# Sheet_1_2025-03-21.net
KiCad netlist of a schematic drawn in Altium Designer
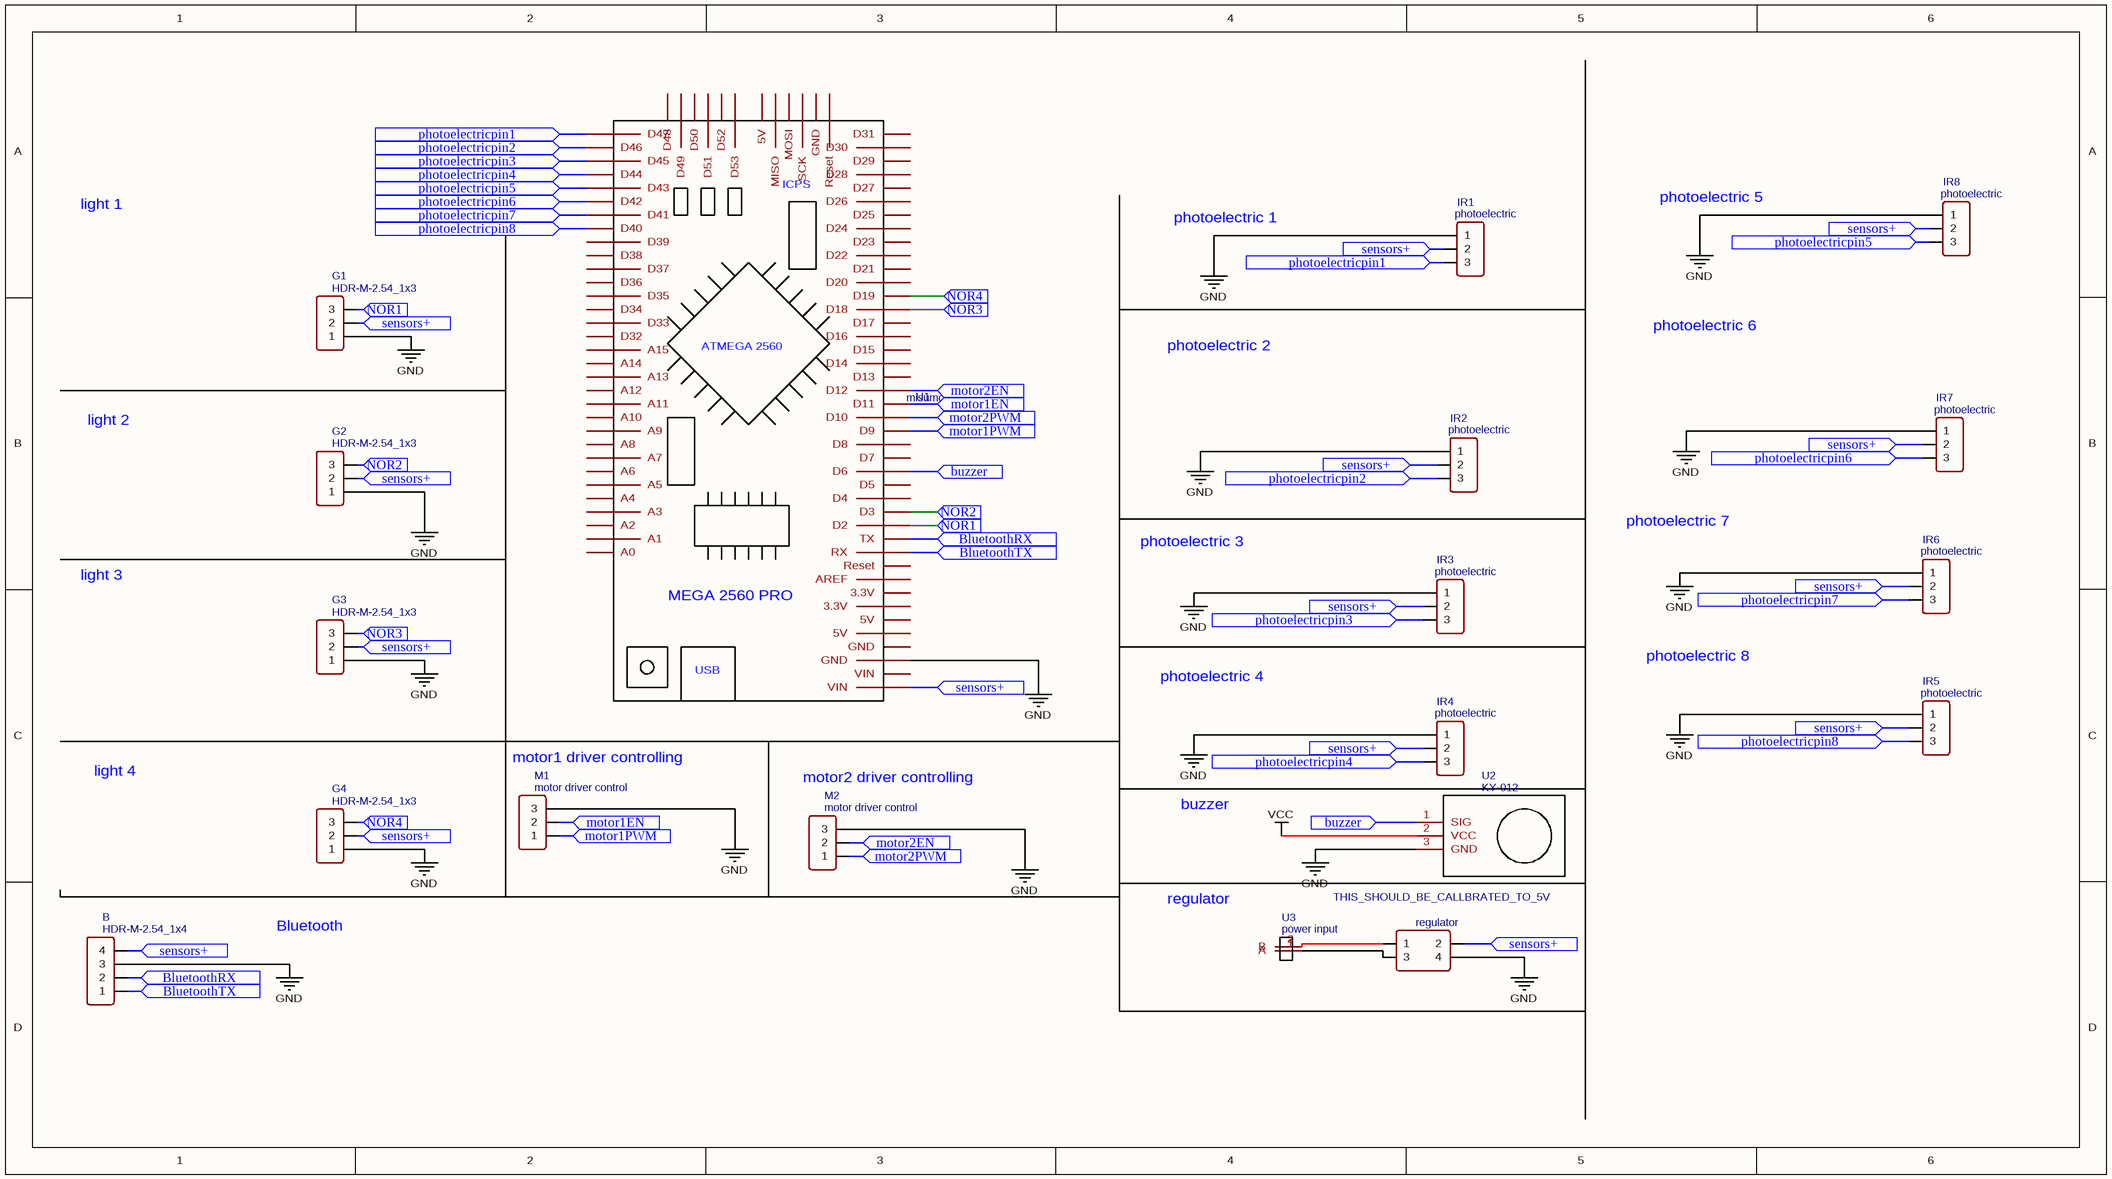
[diagram p0: Sheet_1_2025-03-21.schdoc]

(export (version "E")
  (design (tool "Eeschema 10.0.6"))
  (components
    (comp (ref "B")
      (value "HDR-M-2.54_1x4")
      (fields (field (name "CONTRIBUTOR") "LCEDA_Lib"))
      (libsource (lib "altium-import") (part "root_2_HDR-M-2.54_1x4_"))
    )
    (comp (ref "G1")
      (value "HDR-M-2.54_1x3")
      (fields (field (name "CONTRIBUTOR") "LCEDA_Lib"))
      (libsource (lib "altium-import") (part "root_2_HDR-M-2.54_1x3_"))
    )
    (comp (ref "G2")
      (value "HDR-M-2.54_1x3")
      (fields (field (name "CONTRIBUTOR") "LCEDA_Lib"))
      (libsource (lib "altium-import") (part "root_2_HDR-M-2.54_1x3_"))
    )
    (comp (ref "G3")
      (value "HDR-M-2.54_1x3")
      (fields (field (name "CONTRIBUTOR") "LCEDA_Lib"))
      (libsource (lib "altium-import") (part "root_2_HDR-M-2.54_1x3_"))
    )
    (comp (ref "G4")
      (value "HDR-M-2.54_1x3")
      (fields (field (name "CONTRIBUTOR") "LCEDA_Lib"))
      (libsource (lib "altium-import") (part "root_2_HDR-M-2.54_1x3_"))
    )
    (comp (ref "IR1")
      (value "photoelectric")
      (fields (field (name "CONTRIBUTOR") "LCEDA_Lib"))
      (libsource (lib "altium-import") (part "root_0_photoelectric_"))
    )
    (comp (ref "IR2")
      (value "photoelectric")
      (fields (field (name "CONTRIBUTOR") "LCEDA_Lib"))
      (libsource (lib "altium-import") (part "root_0_photoelectric_"))
    )
    (comp (ref "IR3")
      (value "photoelectric")
      (fields (field (name "CONTRIBUTOR") "LCEDA_Lib"))
      (libsource (lib "altium-import") (part "root_0_photoelectric_"))
    )
    (comp (ref "IR4")
      (value "photoelectric")
      (fields (field (name "CONTRIBUTOR") "LCEDA_Lib"))
      (libsource (lib "altium-import") (part "root_0_photoelectric_"))
    )
    (comp (ref "IR5")
      (value "photoelectric")
      (fields (field (name "CONTRIBUTOR") "LCEDA_Lib"))
      (libsource (lib "altium-import") (part "root_0_photoelectric_"))
    )
    (comp (ref "IR6")
      (value "photoelectric")
      (fields (field (name "CONTRIBUTOR") "LCEDA_Lib"))
      (libsource (lib "altium-import") (part "root_0_photoelectric_"))
    )
    (comp (ref "IR7")
      (value "photoelectric")
      (fields (field (name "CONTRIBUTOR") "LCEDA_Lib"))
      (libsource (lib "altium-import") (part "root_0_photoelectric_"))
    )
    (comp (ref "IR8")
      (value "photoelectric")
      (fields (field (name "CONTRIBUTOR") "LCEDA_Lib"))
      (libsource (lib "altium-import") (part "root_0_photoelectric_"))
    )
    (comp (ref "M1")
      (value "motor driver control")
      (fields (field (name "CONTRIBUTOR") "LCEDA_Lib"))
      (libsource (lib "altium-import") (part "root_2_motor driver control_"))
    )
    (comp (ref "M2")
      (value "motor driver control")
      (fields (field (name "CONTRIBUTOR") "LCEDA_Lib"))
      (libsource (lib "altium-import") (part "root_2_motor driver control_"))
    )
    (comp (ref "THIS_SHOULD_BE_CALLBRATED_TO_5V")
      (value "regulator")
      (fields (field (name "CONTRIBUTOR") "LCEDA_Lib"))
      (libsource (lib "altium-import") (part "root_0_regulator_"))
    )
    (comp (ref "U1")
      (value "misumo potente")
      (fields
        (field (name "MANUFACTURER PART") "Arduino Mega 2560 Pro Mini")
        (field (name "CONTRIBUTOR") "Mauricio Placito Lopez")
      )
      (libsource (lib "altium-import") (part "root_0_misumo potente_"))
    )
    (comp (ref "U2")
      (value "KY-012")
      (fields (field (name "CONTRIBUTOR") "Андрей Кошевой"))
      (libsource (lib "altium-import") (part "root_1_KY-012_"))
    )
    (comp (ref "U3")
      (value "power input")
      (fields
        (field (name "MANUFACTURER") "Phoenix Contact")
        (field (name "MANUFACTURER PART") "1725656")
        (field (name "CONTRIBUTOR") "sm.rial")
      )
      (libsource (lib "altium-import") (part "root_1_power input_"))
    )
  )
  (nets
    (net (code "1") (name "/BluetoothRX") (class "Default")
      (node (ref "B") (pin "2") (pinfunction "2_2") (pintype "passive"))
      (node (ref "U1") (pin "75") (pinfunction "TX_75") (pintype "passive"))
    )
    (net (code "2") (name "/BluetoothTX") (class "Default")
      (node (ref "B") (pin "1") (pinfunction "1_1") (pintype "passive"))
      (node (ref "U1") (pin "76") (pinfunction "RX_76") (pintype "passive"))
    )
    (net (code "3") (name "/NOR1") (class "Default")
      (node (ref "G1") (pin "3") (pinfunction "3_3") (pintype "passive"))
      (node (ref "U1") (pin "74") (pinfunction "D2_74") (pintype "passive"))
    )
    (net (code "4") (name "/NOR2") (class "Default")
      (node (ref "G2") (pin "3") (pinfunction "3_3") (pintype "passive"))
      (node (ref "U1") (pin "73") (pinfunction "D3_73") (pintype "passive"))
    )
    (net (code "5") (name "/NOR3") (class "Default")
      (node (ref "G3") (pin "3") (pinfunction "3_3") (pintype "passive"))
      (node (ref "U1") (pin "58") (pinfunction "D18_58") (pintype "passive"))
    )
    (net (code "6") (name "/NOR4") (class "Default")
      (node (ref "G4") (pin "3") (pinfunction "3_3") (pintype "passive"))
      (node (ref "U1") (pin "57") (pinfunction "D19_57") (pintype "passive"))
    )
    (net (code "7") (name "/buzzer") (class "Default")
      (node (ref "U1") (pin "70") (pinfunction "D6_70") (pintype "passive"))
      (node (ref "U2") (pin "1") (pinfunction "SIG_1") (pintype "passive"))
    )
    (net (code "8") (name "/motor1EN") (class "Default")
      (node (ref "M1") (pin "2") (pinfunction "2_2") (pintype "passive"))
      (node (ref "U1") (pin "65") (pinfunction "D11_65") (pintype "passive"))
    )
    (net (code "9") (name "/motor1PWM") (class "Default")
      (node (ref "M1") (pin "1") (pinfunction "1_1") (pintype "passive"))
      (node (ref "U1") (pin "67") (pinfunction "D9_67") (pintype "passive"))
    )
    (net (code "10") (name "/motor2EN") (class "Default")
      (node (ref "M2") (pin "2") (pinfunction "2_2") (pintype "passive"))
      (node (ref "U1") (pin "64") (pinfunction "D12_64") (pintype "passive"))
    )
    (net (code "11") (name "/motor2PWM") (class "Default")
      (node (ref "M2") (pin "1") (pinfunction "1_1") (pintype "passive"))
      (node (ref "U1") (pin "66") (pinfunction "D10_66") (pintype "passive"))
    )
    (net (code "12") (name "/photoelectricpin1") (class "Default")
      (node (ref "IR1") (pin "3") (pinfunction "3_3") (pintype "passive"))
      (node (ref "U1") (pin "32") (pinfunction "D47_32") (pintype "passive"))
    )
    (net (code "13") (name "/photoelectricpin2") (class "Default")
      (node (ref "IR2") (pin "3") (pinfunction "3_3") (pintype "passive"))
      (node (ref "U1") (pin "31") (pinfunction "D46_31") (pintype "passive"))
    )
    (net (code "14") (name "/photoelectricpin3") (class "Default")
      (node (ref "IR3") (pin "3") (pinfunction "3_3") (pintype "passive"))
      (node (ref "U1") (pin "30") (pinfunction "D45_30") (pintype "passive"))
    )
    (net (code "15") (name "/photoelectricpin4") (class "Default")
      (node (ref "IR4") (pin "3") (pinfunction "3_3") (pintype "passive"))
      (node (ref "U1") (pin "29") (pinfunction "D44_29") (pintype "passive"))
    )
    (net (code "16") (name "/photoelectricpin5") (class "Default")
      (node (ref "IR8") (pin "3") (pinfunction "3_3") (pintype "passive"))
      (node (ref "U1") (pin "28") (pinfunction "D43_28") (pintype "passive"))
    )
    (net (code "17") (name "/photoelectricpin6") (class "Default")
      (node (ref "IR7") (pin "3") (pinfunction "3_3") (pintype "passive"))
      (node (ref "U1") (pin "27") (pinfunction "D42_27") (pintype "passive"))
    )
    (net (code "18") (name "/photoelectricpin7") (class "Default")
      (node (ref "IR6") (pin "3") (pinfunction "3_3") (pintype "passive"))
      (node (ref "U1") (pin "26") (pinfunction "D41_26") (pintype "passive"))
    )
    (net (code "19") (name "/photoelectricpin8") (class "Default")
      (node (ref "IR5") (pin "3") (pinfunction "3_3") (pintype "passive"))
      (node (ref "U1") (pin "25") (pinfunction "D40_25") (pintype "passive"))
    )
    (net (code "20") (name "/sensors+") (class "Default")
      (node (ref "B") (pin "4") (pinfunction "4_4") (pintype "passive"))
      (node (ref "G1") (pin "2") (pinfunction "2_2") (pintype "passive"))
      (node (ref "G2") (pin "2") (pinfunction "2_2") (pintype "passive"))
      (node (ref "G3") (pin "2") (pinfunction "2_2") (pintype "passive"))
      (node (ref "G4") (pin "2") (pinfunction "2_2") (pintype "passive"))
      (node (ref "IR1") (pin "2") (pinfunction "2_2") (pintype "passive"))
      (node (ref "IR2") (pin "2") (pinfunction "2_2") (pintype "passive"))
      (node (ref "IR3") (pin "2") (pinfunction "2_2") (pintype "passive"))
      (node (ref "IR4") (pin "2") (pinfunction "2_2") (pintype "passive"))
      (node (ref "IR5") (pin "2") (pinfunction "2_2") (pintype "passive"))
      (node (ref "IR6") (pin "2") (pinfunction "2_2") (pintype "passive"))
      (node (ref "IR7") (pin "2") (pinfunction "2_2") (pintype "passive"))
      (node (ref "IR8") (pin "2") (pinfunction "2_2") (pintype "passive"))
      (node (ref "THIS_SHOULD_BE_CALLBRATED_TO_5V") (pin "2") (pinfunction "2_2") (pintype "passive"))
      (node (ref "U1") (pin "86") (pinfunction "VIN_86") (pintype "passive"))
    )
    (net (code "21") (name "GND") (class "Default")
      (node (ref "B") (pin "3") (pinfunction "3_3") (pintype "passive"))
      (node (ref "G1") (pin "1") (pinfunction "1_1") (pintype "passive"))
      (node (ref "G2") (pin "1") (pinfunction "1_1") (pintype "passive"))
      (node (ref "G3") (pin "1") (pinfunction "1_1") (pintype "passive"))
      (node (ref "G4") (pin "1") (pinfunction "1_1") (pintype "passive"))
      (node (ref "IR1") (pin "1") (pinfunction "1_1") (pintype "passive"))
      (node (ref "IR2") (pin "1") (pinfunction "1_1") (pintype "passive"))
      (node (ref "IR3") (pin "1") (pinfunction "1_1") (pintype "passive"))
      (node (ref "IR4") (pin "1") (pinfunction "1_1") (pintype "passive"))
      (node (ref "IR5") (pin "1") (pinfunction "1_1") (pintype "passive"))
      (node (ref "IR6") (pin "1") (pinfunction "1_1") (pintype "passive"))
      (node (ref "IR7") (pin "1") (pinfunction "1_1") (pintype "passive"))
      (node (ref "IR8") (pin "1") (pinfunction "1_1") (pintype "passive"))
      (node (ref "M1") (pin "3") (pinfunction "3_3") (pintype "passive"))
      (node (ref "M2") (pin "3") (pinfunction "3_3") (pintype "passive"))
      (node (ref "THIS_SHOULD_BE_CALLBRATED_TO_5V") (pin "4") (pinfunction "4_4") (pintype "passive"))
      (node (ref "U1") (pin "84") (pinfunction "GND_84") (pintype "passive"))
      (node (ref "U2") (pin "3") (pinfunction "GND_3") (pintype "passive"))
    )
    (net (code "22") (name "Net-(U3-A)") (class "Default")
      (node (ref "THIS_SHOULD_BE_CALLBRATED_TO_5V") (pin "3") (pinfunction "3_3") (pintype "passive"))
      (node (ref "U3") (pin "1") (pinfunction "A_1") (pintype "passive"))
    )
    (net (code "23") (name "Net-(U3-B)") (class "Default")
      (node (ref "THIS_SHOULD_BE_CALLBRATED_TO_5V") (pin "1") (pinfunction "1_1") (pintype "passive"))
      (node (ref "U3") (pin "2") (pinfunction "B_2") (pintype "passive"))
    )
    (net (code "24") (name "VCC") (class "Default")
      (node (ref "U2") (pin "2") (pinfunction "VCC_2") (pintype "passive"))
    )
    (net (code "25") (name "unconnected-(U1-3.3V-Pad79)") (class "Default")
      (node (ref "U1") (pin "79") (pinfunction "3.3V_79") (pintype "passive"))
    )
    (net (code "26") (name "unconnected-(U1-3.3V-Pad80)") (class "Default")
      (node (ref "U1") (pin "80") (pinfunction "3.3V_80") (pintype "passive"))
    )
    (net (code "27") (name "unconnected-(U1-5V-Pad39)") (class "Default")
      (node (ref "U1") (pin "39") (pinfunction "5V_39") (pintype "passive"))
    )
    (net (code "28") (name "unconnected-(U1-5V-Pad81)") (class "Default")
      (node (ref "U1") (pin "81") (pinfunction "5V_81") (pintype "passive"))
    )
    (net (code "29") (name "unconnected-(U1-5V-Pad82)") (class "Default")
      (node (ref "U1") (pin "82") (pinfunction "5V_82") (pintype "passive"))
    )
    (net (code "30") (name "unconnected-(U1-A0-Pad1)") (class "Default")
      (node (ref "U1") (pin "1") (pinfunction "A0_1") (pintype "passive"))
    )
    (net (code "31") (name "unconnected-(U1-A1-Pad2)") (class "Default")
      (node (ref "U1") (pin "2") (pinfunction "A1_2") (pintype "passive"))
    )
    (net (code "32") (name "unconnected-(U1-A2-Pad3)") (class "Default")
      (node (ref "U1") (pin "3") (pinfunction "A2_3") (pintype "passive"))
    )
    (net (code "33") (name "unconnected-(U1-A3-Pad4)") (class "Default")
      (node (ref "U1") (pin "4") (pinfunction "A3_4") (pintype "passive"))
    )
    (net (code "34") (name "unconnected-(U1-A4-Pad5)") (class "Default")
      (node (ref "U1") (pin "5") (pinfunction "A4_5") (pintype "passive"))
    )
    (net (code "35") (name "unconnected-(U1-A5-Pad6)") (class "Default")
      (node (ref "U1") (pin "6") (pinfunction "A5_6") (pintype "passive"))
    )
    (net (code "36") (name "unconnected-(U1-A6-Pad7)") (class "Default")
      (node (ref "U1") (pin "7") (pinfunction "A6_7") (pintype "passive"))
    )
    (net (code "37") (name "unconnected-(U1-A7-Pad8)") (class "Default")
      (node (ref "U1") (pin "8") (pinfunction "A7_8") (pintype "passive"))
    )
    (net (code "38") (name "unconnected-(U1-A8-Pad9)") (class "Default")
      (node (ref "U1") (pin "9") (pinfunction "A8_9") (pintype "passive"))
    )
    (net (code "39") (name "unconnected-(U1-A9-Pad10)") (class "Default")
      (node (ref "U1") (pin "10") (pinfunction "A9_10") (pintype "passive"))
    )
    (net (code "40") (name "unconnected-(U1-A10-Pad11)") (class "Default")
      (node (ref "U1") (pin "11") (pinfunction "A10_11") (pintype "passive"))
    )
    (net (code "41") (name "unconnected-(U1-A11-Pad12)") (class "Default")
      (node (ref "U1") (pin "12") (pinfunction "A11_12") (pintype "passive"))
    )
    (net (code "42") (name "unconnected-(U1-A12-Pad13)") (class "Default")
      (node (ref "U1") (pin "13") (pinfunction "A12_13") (pintype "passive"))
    )
    (net (code "43") (name "unconnected-(U1-A13-Pad14)") (class "Default")
      (node (ref "U1") (pin "14") (pinfunction "A13_14") (pintype "passive"))
    )
    (net (code "44") (name "unconnected-(U1-A14-Pad15)") (class "Default")
      (node (ref "U1") (pin "15") (pinfunction "A14_15") (pintype "passive"))
    )
    (net (code "45") (name "unconnected-(U1-A15-Pad16)") (class "Default")
      (node (ref "U1") (pin "16") (pinfunction "A15_16") (pintype "passive"))
    )
    (net (code "46") (name "unconnected-(U1-AREF-Pad78)") (class "Default")
      (node (ref "U1") (pin "78") (pinfunction "AREF_78") (pintype "passive"))
    )
    (net (code "47") (name "unconnected-(U1-D4-Pad72)") (class "Default")
      (node (ref "U1") (pin "72") (pinfunction "D4_72") (pintype "passive"))
    )
    (net (code "48") (name "unconnected-(U1-D5-Pad71)") (class "Default")
      (node (ref "U1") (pin "71") (pinfunction "D5_71") (pintype "passive"))
    )
    (net (code "49") (name "unconnected-(U1-D7-Pad69)") (class "Default")
      (node (ref "U1") (pin "69") (pinfunction "D7_69") (pintype "passive"))
    )
    (net (code "50") (name "unconnected-(U1-D8-Pad68)") (class "Default")
      (node (ref "U1") (pin "68") (pinfunction "D8_68") (pintype "passive"))
    )
    (net (code "51") (name "unconnected-(U1-D13-Pad63)") (class "Default")
      (node (ref "U1") (pin "63") (pinfunction "D13_63") (pintype "passive"))
    )
    (net (code "52") (name "unconnected-(U1-D14-Pad62)") (class "Default")
      (node (ref "U1") (pin "62") (pinfunction "D14_62") (pintype "passive"))
    )
    (net (code "53") (name "unconnected-(U1-D15-Pad61)") (class "Default")
      (node (ref "U1") (pin "61") (pinfunction "D15_61") (pintype "passive"))
    )
    (net (code "54") (name "unconnected-(U1-D16-Pad60)") (class "Default")
      (node (ref "U1") (pin "60") (pinfunction "D16_60") (pintype "passive"))
    )
    (net (code "55") (name "unconnected-(U1-D17-Pad59)") (class "Default")
      (node (ref "U1") (pin "59") (pinfunction "D17_59") (pintype "passive"))
    )
    (net (code "56") (name "unconnected-(U1-D20-Pad56)") (class "Default")
      (node (ref "U1") (pin "56") (pinfunction "D20_56") (pintype "passive"))
    )
    (net (code "57") (name "unconnected-(U1-D21-Pad55)") (class "Default")
      (node (ref "U1") (pin "55") (pinfunction "D21_55") (pintype "passive"))
    )
    (net (code "58") (name "unconnected-(U1-D22-Pad54)") (class "Default")
      (node (ref "U1") (pin "54") (pinfunction "D22_54") (pintype "passive"))
    )
    (net (code "59") (name "unconnected-(U1-D23-Pad53)") (class "Default")
      (node (ref "U1") (pin "53") (pinfunction "D23_53") (pintype "passive"))
    )
    (net (code "60") (name "unconnected-(U1-D24-Pad52)") (class "Default")
      (node (ref "U1") (pin "52") (pinfunction "D24_52") (pintype "passive"))
    )
    (net (code "61") (name "unconnected-(U1-D25-Pad51)") (class "Default")
      (node (ref "U1") (pin "51") (pinfunction "D25_51") (pintype "passive"))
    )
    (net (code "62") (name "unconnected-(U1-D26-Pad50)") (class "Default")
      (node (ref "U1") (pin "50") (pinfunction "D26_50") (pintype "passive"))
    )
    (net (code "63") (name "unconnected-(U1-D27-Pad49)") (class "Default")
      (node (ref "U1") (pin "49") (pinfunction "D27_49") (pintype "passive"))
    )
    (net (code "64") (name "unconnected-(U1-D28-Pad48)") (class "Default")
      (node (ref "U1") (pin "48") (pinfunction "D28_48") (pintype "passive"))
    )
    (net (code "65") (name "unconnected-(U1-D29-Pad47)") (class "Default")
      (node (ref "U1") (pin "47") (pinfunction "D29_47") (pintype "passive"))
    )
    (net (code "66") (name "unconnected-(U1-D30-Pad46)") (class "Default")
      (node (ref "U1") (pin "46") (pinfunction "D30_46") (pintype "passive"))
    )
    (net (code "67") (name "unconnected-(U1-D31-Pad45)") (class "Default")
      (node (ref "U1") (pin "45") (pinfunction "D31_45") (pintype "passive"))
    )
    (net (code "68") (name "unconnected-(U1-D32-Pad17)") (class "Default")
      (node (ref "U1") (pin "17") (pinfunction "D32_17") (pintype "passive"))
    )
    (net (code "69") (name "unconnected-(U1-D33-Pad18)") (class "Default")
      (node (ref "U1") (pin "18") (pinfunction "D33_18") (pintype "passive"))
    )
    (net (code "70") (name "unconnected-(U1-D34-Pad19)") (class "Default")
      (node (ref "U1") (pin "19") (pinfunction "D34_19") (pintype "passive"))
    )
    (net (code "71") (name "unconnected-(U1-D35-Pad20)") (class "Default")
      (node (ref "U1") (pin "20") (pinfunction "D35_20") (pintype "passive"))
    )
    (net (code "72") (name "unconnected-(U1-D36-Pad21)") (class "Default")
      (node (ref "U1") (pin "21") (pinfunction "D36_21") (pintype "passive"))
    )
    (net (code "73") (name "unconnected-(U1-D37-Pad22)") (class "Default")
      (node (ref "U1") (pin "22") (pinfunction "D37_22") (pintype "passive"))
    )
    (net (code "74") (name "unconnected-(U1-D38-Pad23)") (class "Default")
      (node (ref "U1") (pin "23") (pinfunction "D38_23") (pintype "passive"))
    )
    (net (code "75") (name "unconnected-(U1-D39-Pad24)") (class "Default")
      (node (ref "U1") (pin "24") (pinfunction "D39_24") (pintype "passive"))
    )
    (net (code "76") (name "unconnected-(U1-D48-Pad33)") (class "Default")
      (node (ref "U1") (pin "33") (pinfunction "D48_33") (pintype "passive"))
    )
    (net (code "77") (name "unconnected-(U1-D49-Pad34)") (class "Default")
      (node (ref "U1") (pin "34") (pinfunction "D49_34") (pintype "passive"))
    )
    (net (code "78") (name "unconnected-(U1-D50-Pad35)") (class "Default")
      (node (ref "U1") (pin "35") (pinfunction "D50_35") (pintype "passive"))
    )
    (net (code "79") (name "unconnected-(U1-D51-Pad36)") (class "Default")
      (node (ref "U1") (pin "36") (pinfunction "D51_36") (pintype "passive"))
    )
    (net (code "80") (name "unconnected-(U1-D52-Pad37)") (class "Default")
      (node (ref "U1") (pin "37") (pinfunction "D52_37") (pintype "passive"))
    )
    (net (code "81") (name "unconnected-(U1-D53-Pad38)") (class "Default")
      (node (ref "U1") (pin "38") (pinfunction "D53_38") (pintype "passive"))
    )
    (net (code "82") (name "unconnected-(U1-GND-Pad43)") (class "Default")
      (node (ref "U1") (pin "43") (pinfunction "GND_43") (pintype "passive"))
    )
    (net (code "83") (name "unconnected-(U1-GND-Pad83)") (class "Default")
      (node (ref "U1") (pin "83") (pinfunction "GND_83") (pintype "passive"))
    )
    (net (code "84") (name "unconnected-(U1-MISO-Pad40)") (class "Default")
      (node (ref "U1") (pin "40") (pinfunction "MISO_40") (pintype "passive"))
    )
    (net (code "85") (name "unconnected-(U1-MOSI-Pad41)") (class "Default")
      (node (ref "U1") (pin "41") (pinfunction "MOSI_41") (pintype "passive"))
    )
    (net (code "86") (name "unconnected-(U1-Reset-Pad44)") (class "Default")
      (node (ref "U1") (pin "44") (pinfunction "Reset_44") (pintype "passive"))
    )
    (net (code "87") (name "unconnected-(U1-Reset-Pad77)") (class "Default")
      (node (ref "U1") (pin "77") (pinfunction "Reset_77") (pintype "passive"))
    )
    (net (code "88") (name "unconnected-(U1-SCK-Pad42)") (class "Default")
      (node (ref "U1") (pin "42") (pinfunction "SCK_42") (pintype "passive"))
    )
    (net (code "89") (name "unconnected-(U1-VIN-Pad85)") (class "Default")
      (node (ref "U1") (pin "85") (pinfunction "VIN_85") (pintype "passive"))
    )
  )
)
